# InterfacesB_Decoupling.net
KiCad netlist of a schematic drawn in Altium Designer
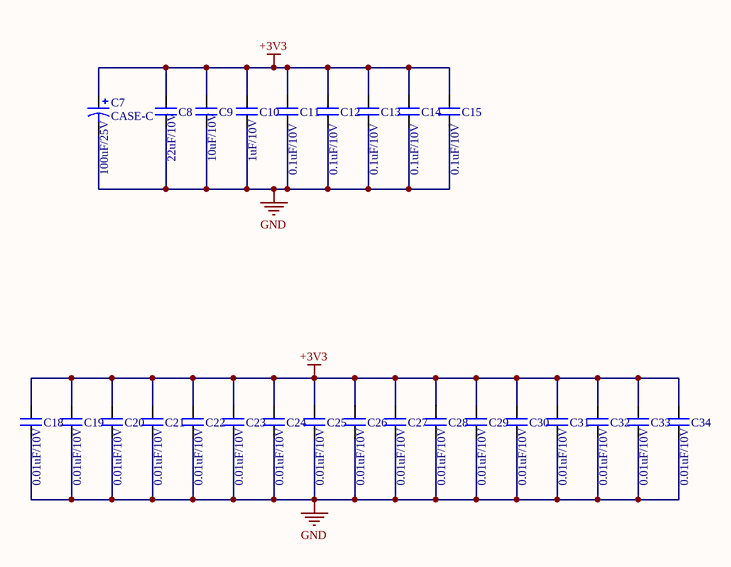
[diagram p0: InterfacesB_Decoupling.SchDoc]

(export (version "E")
  (design (tool "Eeschema 10.0.6"))
  (components
    (comp (ref "C7")
      (value "CASE-C")
      (footprint "CASE-C")
      (fields (field (name "ALTIUM_VALUE") "100uF/25V"))
      (libsource (lib "AdapterLib") (part "CASE-C"))
    )
    (comp (ref "C8")
      (value "22uF/10V")
      (footprint "CAP_0805")
      (fields (field (name "Comment") "CAP_0805"))
      (libsource (lib "AdapterLib") (part "CAP_0805"))
    )
    (comp (ref "C9")
      (value "10uF/10V")
      (footprint "CAP_0805")
      (fields (field (name "Comment") "CAP_0805"))
      (libsource (lib "AdapterLib") (part "CAP_0805"))
    )
    (comp (ref "C10")
      (value "1uF/10V")
      (footprint "CAP_0805")
      (fields (field (name "Comment") "CAP_0805"))
      (libsource (lib "AdapterLib") (part "CAP_0805"))
    )
    (comp (ref "C11")
      (value "0.1uF/10V")
      (footprint "CAP_0805")
      (fields (field (name "Comment") "CAP_0805"))
      (libsource (lib "AdapterLib") (part "CAP_0805"))
    )
    (comp (ref "C12")
      (value "0.1uF/10V")
      (footprint "CAP_0805")
      (fields (field (name "Comment") "CAP_0805"))
      (libsource (lib "AdapterLib") (part "CAP_0805"))
    )
    (comp (ref "C13")
      (value "0.1uF/10V")
      (footprint "CAP_0805")
      (fields (field (name "Comment") "CAP_0805"))
      (libsource (lib "AdapterLib") (part "CAP_0805"))
    )
    (comp (ref "C14")
      (value "0.1uF/10V")
      (footprint "CAP_0805")
      (fields (field (name "Comment") "CAP_0805"))
      (libsource (lib "AdapterLib") (part "CAP_0805"))
    )
    (comp (ref "C15")
      (value "0.1uF/10V")
      (footprint "CAP_0805")
      (fields (field (name "Comment") "CAP_0805"))
      (libsource (lib "AdapterLib") (part "CAP_0805"))
    )
    (comp (ref "C18")
      (value "0.01uF/10V")
      (footprint "CAP_0805")
      (fields (field (name "Comment") "CAP_0805"))
      (libsource (lib "AdapterLib") (part "CAP_0805"))
    )
    (comp (ref "C19")
      (value "0.01uF/10V")
      (footprint "CAP_0805")
      (fields (field (name "Comment") "CAP_0805"))
      (libsource (lib "AdapterLib") (part "CAP_0805"))
    )
    (comp (ref "C20")
      (value "0.01uF/10V")
      (footprint "CAP_0805")
      (fields (field (name "Comment") "CAP_0805"))
      (libsource (lib "AdapterLib") (part "CAP_0805"))
    )
    (comp (ref "C21")
      (value "0.01uF/10V")
      (footprint "CAP_0805")
      (fields (field (name "Comment") "CAP_0805"))
      (libsource (lib "AdapterLib") (part "CAP_0805"))
    )
    (comp (ref "C22")
      (value "0.01uF/10V")
      (footprint "CAP_0805")
      (fields (field (name "Comment") "CAP_0805"))
      (libsource (lib "AdapterLib") (part "CAP_0805"))
    )
    (comp (ref "C23")
      (value "0.01uF/10V")
      (footprint "CAP_0805")
      (fields (field (name "Comment") "CAP_0805"))
      (libsource (lib "AdapterLib") (part "CAP_0805"))
    )
    (comp (ref "C24")
      (value "0.01uF/10V")
      (footprint "CAP_0805")
      (fields (field (name "Comment") "CAP_0805"))
      (libsource (lib "AdapterLib") (part "CAP_0805"))
    )
    (comp (ref "C25")
      (value "0.01uF/10V")
      (footprint "CAP_0805")
      (fields (field (name "Comment") "CAP_0805"))
      (libsource (lib "AdapterLib") (part "CAP_0805"))
    )
    (comp (ref "C26")
      (value "0.01uF/10V")
      (footprint "CAP_0805")
      (fields (field (name "Comment") "CAP_0805"))
      (libsource (lib "AdapterLib") (part "CAP_0805"))
    )
    (comp (ref "C27")
      (value "0.01uF/10V")
      (footprint "CAP_0805")
      (fields (field (name "Comment") "CAP_0805"))
      (libsource (lib "AdapterLib") (part "CAP_0805"))
    )
    (comp (ref "C28")
      (value "0.01uF/10V")
      (footprint "CAP_0805")
      (fields (field (name "Comment") "CAP_0805"))
      (libsource (lib "AdapterLib") (part "CAP_0805"))
    )
    (comp (ref "C29")
      (value "0.01uF/10V")
      (footprint "CAP_0805")
      (fields (field (name "Comment") "CAP_0805"))
      (libsource (lib "AdapterLib") (part "CAP_0805"))
    )
    (comp (ref "C30")
      (value "0.01uF/10V")
      (footprint "CAP_0805")
      (fields (field (name "Comment") "CAP_0805"))
      (libsource (lib "AdapterLib") (part "CAP_0805"))
    )
    (comp (ref "C31")
      (value "0.01uF/10V")
      (footprint "CAP_0805")
      (fields (field (name "Comment") "CAP_0805"))
      (libsource (lib "AdapterLib") (part "CAP_0805"))
    )
    (comp (ref "C32")
      (value "0.01uF/10V")
      (footprint "CAP_0805")
      (fields (field (name "Comment") "CAP_0805"))
      (libsource (lib "AdapterLib") (part "CAP_0805"))
    )
    (comp (ref "C33")
      (value "0.01uF/10V")
      (footprint "CAP_0805")
      (fields (field (name "Comment") "CAP_0805"))
      (libsource (lib "AdapterLib") (part "CAP_0805"))
    )
    (comp (ref "C34")
      (value "0.01uF/10V")
      (footprint "CAP_0805")
      (fields (field (name "Comment") "CAP_0805"))
      (libsource (lib "AdapterLib") (part "CAP_0805"))
    )
  )
  (nets
    (net (code "1") (name "+3V3") (class "Default")
      (node (ref "C10") (pin "2") (pinfunction "2_2") (pintype "passive"))
      (node (ref "C11") (pin "2") (pinfunction "2_2") (pintype "passive"))
      (node (ref "C12") (pin "2") (pinfunction "2_2") (pintype "passive"))
      (node (ref "C13") (pin "2") (pinfunction "2_2") (pintype "passive"))
      (node (ref "C14") (pin "2") (pinfunction "2_2") (pintype "passive"))
      (node (ref "C15") (pin "2") (pinfunction "2_2") (pintype "passive"))
      (node (ref "C18") (pin "2") (pinfunction "2_2") (pintype "passive"))
      (node (ref "C19") (pin "2") (pinfunction "2_2") (pintype "passive"))
      (node (ref "C20") (pin "2") (pinfunction "2_2") (pintype "passive"))
      (node (ref "C21") (pin "2") (pinfunction "2_2") (pintype "passive"))
      (node (ref "C22") (pin "2") (pinfunction "2_2") (pintype "passive"))
      (node (ref "C23") (pin "2") (pinfunction "2_2") (pintype "passive"))
      (node (ref "C24") (pin "2") (pinfunction "2_2") (pintype "passive"))
      (node (ref "C25") (pin "2") (pinfunction "2_2") (pintype "passive"))
      (node (ref "C26") (pin "2") (pinfunction "2_2") (pintype "passive"))
      (node (ref "C27") (pin "2") (pinfunction "2_2") (pintype "passive"))
      (node (ref "C28") (pin "2") (pinfunction "2_2") (pintype "passive"))
      (node (ref "C29") (pin "2") (pinfunction "2_2") (pintype "passive"))
      (node (ref "C30") (pin "2") (pinfunction "2_2") (pintype "passive"))
      (node (ref "C31") (pin "2") (pinfunction "2_2") (pintype "passive"))
      (node (ref "C32") (pin "2") (pinfunction "2_2") (pintype "passive"))
      (node (ref "C33") (pin "2") (pinfunction "2_2") (pintype "passive"))
      (node (ref "C34") (pin "2") (pinfunction "2_2") (pintype "passive"))
      (node (ref "C7") (pin "A") (pinfunction "1_A") (pintype "passive"))
      (node (ref "C8") (pin "2") (pinfunction "2_2") (pintype "passive"))
      (node (ref "C9") (pin "2") (pinfunction "2_2") (pintype "passive"))
    )
    (net (code "2") (name "GND") (class "Default")
      (node (ref "C10") (pin "1") (pinfunction "1_1") (pintype "passive"))
      (node (ref "C11") (pin "1") (pinfunction "1_1") (pintype "passive"))
      (node (ref "C12") (pin "1") (pinfunction "1_1") (pintype "passive"))
      (node (ref "C13") (pin "1") (pinfunction "1_1") (pintype "passive"))
      (node (ref "C14") (pin "1") (pinfunction "1_1") (pintype "passive"))
      (node (ref "C15") (pin "1") (pinfunction "1_1") (pintype "passive"))
      (node (ref "C18") (pin "1") (pinfunction "1_1") (pintype "passive"))
      (node (ref "C19") (pin "1") (pinfunction "1_1") (pintype "passive"))
      (node (ref "C20") (pin "1") (pinfunction "1_1") (pintype "passive"))
      (node (ref "C21") (pin "1") (pinfunction "1_1") (pintype "passive"))
      (node (ref "C22") (pin "1") (pinfunction "1_1") (pintype "passive"))
      (node (ref "C23") (pin "1") (pinfunction "1_1") (pintype "passive"))
      (node (ref "C24") (pin "1") (pinfunction "1_1") (pintype "passive"))
      (node (ref "C25") (pin "1") (pinfunction "1_1") (pintype "passive"))
      (node (ref "C26") (pin "1") (pinfunction "1_1") (pintype "passive"))
      (node (ref "C27") (pin "1") (pinfunction "1_1") (pintype "passive"))
      (node (ref "C28") (pin "1") (pinfunction "1_1") (pintype "passive"))
      (node (ref "C29") (pin "1") (pinfunction "1_1") (pintype "passive"))
      (node (ref "C30") (pin "1") (pinfunction "1_1") (pintype "passive"))
      (node (ref "C31") (pin "1") (pinfunction "1_1") (pintype "passive"))
      (node (ref "C32") (pin "1") (pinfunction "1_1") (pintype "passive"))
      (node (ref "C33") (pin "1") (pinfunction "1_1") (pintype "passive"))
      (node (ref "C34") (pin "1") (pinfunction "1_1") (pintype "passive"))
      (node (ref "C7") (pin "K") (pinfunction "2_K") (pintype "passive"))
      (node (ref "C8") (pin "1") (pinfunction "1_1") (pintype "passive"))
      (node (ref "C9") (pin "1") (pinfunction "1_1") (pintype "passive"))
    )
  )
)
